# STorM32_NT_imu_module_v008-mpu6000.net
KiCad netlist of a schematic drawn in EAGLE
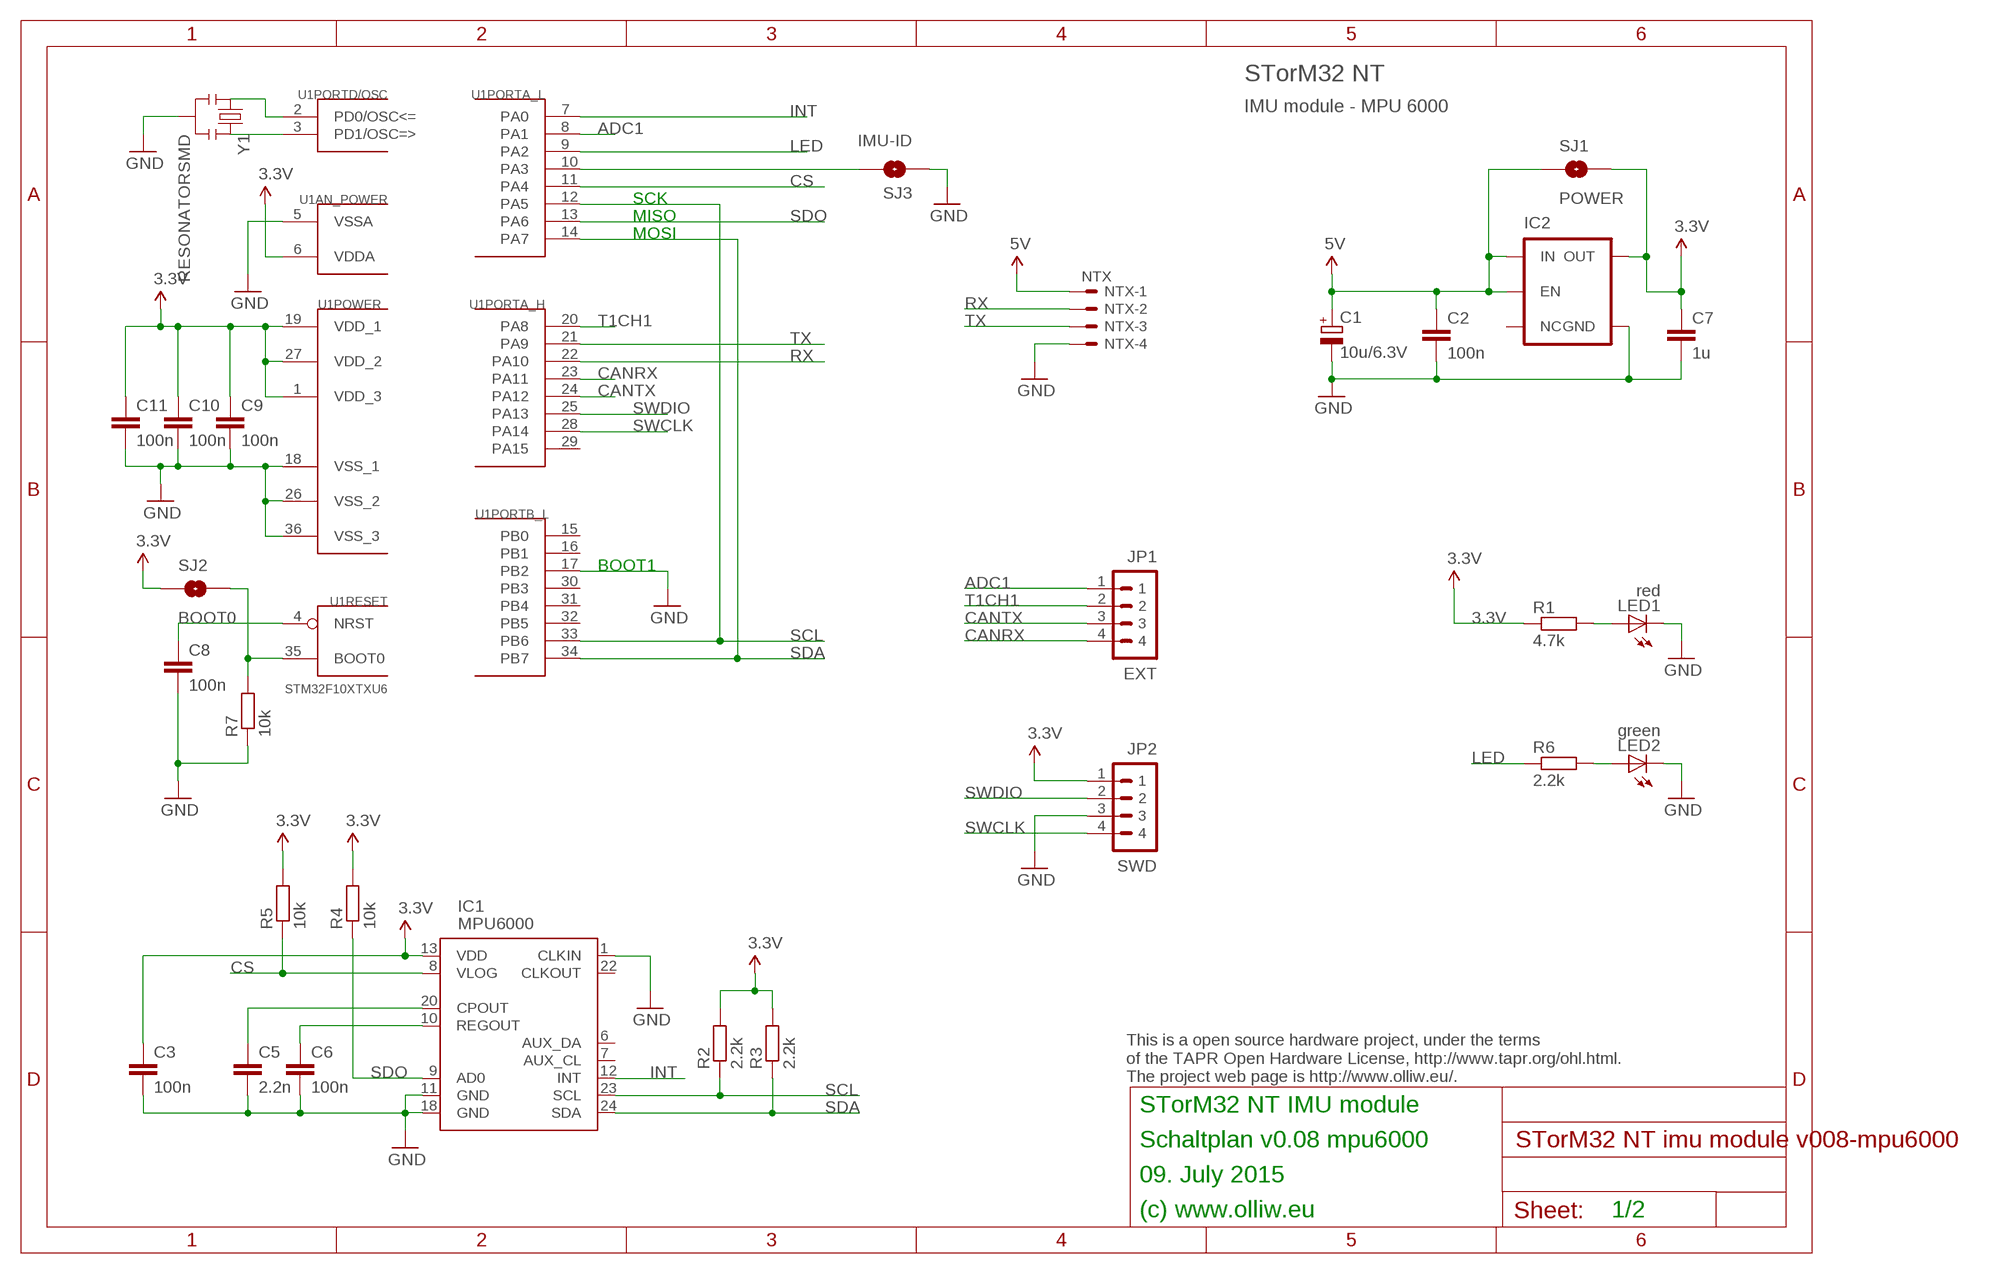
[diagram p0: schematic, sheet 1]

(export (version "E")
  (design (tool "Eeschema 10.0.6"))
  (components
    (comp (ref "C1")
      (value "10u/6.3V")
      (footprint "eagle-import:SMC_B")
      (libsource (lib "eagle-import") (part "CPOL-EUSMCB"))
    )
    (comp (ref "C2")
      (value "100n")
      (footprint "eagle-import:C0603")
      (libsource (lib "eagle-import") (part "C-EUC0603"))
    )
    (comp (ref "C3")
      (value "100n")
      (footprint "eagle-import:C0603")
      (libsource (lib "eagle-import") (part "C-EUC0603"))
    )
    (comp (ref "C5")
      (value "2.2n")
      (footprint "eagle-import:C0603")
      (libsource (lib "eagle-import") (part "C-EUC0603"))
    )
    (comp (ref "C6")
      (value "100n")
      (footprint "eagle-import:C0603")
      (libsource (lib "eagle-import") (part "C-EUC0603"))
    )
    (comp (ref "C7")
      (value "1u")
      (footprint "eagle-import:C0603")
      (libsource (lib "eagle-import") (part "C-EUC0603"))
    )
    (comp (ref "C8")
      (value "100n")
      (footprint "eagle-import:C0402")
      (libsource (lib "eagle-import") (part "C-EUC0402"))
    )
    (comp (ref "C9")
      (value "100n")
      (footprint "eagle-import:C0603")
      (libsource (lib "eagle-import") (part "C-EUC0603"))
    )
    (comp (ref "C10")
      (value "100n")
      (footprint "eagle-import:C0402")
      (libsource (lib "eagle-import") (part "C-EUC0402"))
    )
    (comp (ref "C11")
      (value "100n")
      (footprint "eagle-import:C0603")
      (libsource (lib "eagle-import") (part "C-EUC0603"))
    )
    (comp (ref "IC1")
      (value "MPU6000")
      (footprint "eagle-import:QFN-24")
      (libsource (lib "eagle-import") (part "IMU3000"))
    )
    (comp (ref "IC2")
      (value "V_REG_TPS76433SOT23-5")
      (footprint "eagle-import:SOT23-5")
      (libsource (lib "eagle-import") (part "V_REG_TPS76433SOT23-5"))
    )
    (comp (ref "JP1")
      (value "EXT")
      (footprint "eagle-import:4X1_1P27_OCT_BILEX")
      (libsource (lib "eagle-import") (part "P4X1_1P27-OCT_BILEX"))
    )
    (comp (ref "JP2")
      (value "SWD")
      (footprint "eagle-import:4X1_1P27_OCT_BILEX")
      (libsource (lib "eagle-import") (part "P4X1_1P27-OCT_BILEX"))
    )
    (comp (ref "LED1")
      (value "red")
      (footprint "eagle-import:CHIPLED_0603")
      (libsource (lib "eagle-import") (part "LEDCHIPLED_0603"))
    )
    (comp (ref "LED2")
      (value "green")
      (footprint "eagle-import:CHIPLED_0603")
      (libsource (lib "eagle-import") (part "LEDCHIPLED_0603"))
    )
    (comp (ref "NTX")
      (value "NTX")
      (footprint "eagle-import:SM04B-SRSS-TB")
      (libsource (lib "eagle-import") (part "?M04B-SRSS-TBS"))
    )
    (comp (ref "R1")
      (value "4.7k")
      (footprint "eagle-import:R0603")
      (libsource (lib "eagle-import") (part "R-EU_R0603"))
    )
    (comp (ref "R2")
      (value "2.2k")
      (footprint "eagle-import:R0603")
      (libsource (lib "eagle-import") (part "R-EU_R0603"))
    )
    (comp (ref "R3")
      (value "2.2k")
      (footprint "eagle-import:R0603")
      (libsource (lib "eagle-import") (part "R-EU_R0603"))
    )
    (comp (ref "R4")
      (value "10k")
      (footprint "eagle-import:R0603")
      (libsource (lib "eagle-import") (part "R-EU_R0603"))
    )
    (comp (ref "R5")
      (value "10k")
      (footprint "eagle-import:R0603")
      (libsource (lib "eagle-import") (part "R-EU_R0603"))
    )
    (comp (ref "R6")
      (value "2.2k")
      (footprint "eagle-import:R0603")
      (libsource (lib "eagle-import") (part "R-EU_R0603"))
    )
    (comp (ref "R7")
      (value "10k")
      (footprint "eagle-import:R0603")
      (libsource (lib "eagle-import") (part "R-EU_R0603"))
    )
    (comp (ref "SJ1")
      (value "POWER")
      (footprint "eagle-import:SJ_2S-NO")
      (libsource (lib "eagle-import") (part "SOLDERJUMPERNO"))
    )
    (comp (ref "SJ2")
      (value "BOOT0")
      (footprint "eagle-import:SJ_2S-NO")
      (libsource (lib "eagle-import") (part "SOLDERJUMPERNO"))
    )
    (comp (ref "SJ3")
      (value "IMU-ID")
      (footprint "eagle-import:SJ_2S-NO")
      (libsource (lib "eagle-import") (part "SOLDERJUMPERNO"))
    )
    (comp (ref "U1")
      (value "STM32F10XTXU6")
      (footprint "eagle-import:VFQFPN36")
      (libsource (lib "eagle-import") (part "STM32F10XTXU6"))
    )
    (comp (ref "Y1")
      (value "RESONATORSMD")
      (footprint "eagle-import:RESONATOR-SMD")
      (libsource (lib "eagle-import") (part "RESONATORSMD"))
    )
  )
  (nets
    (net (code "1") (name "/ADC1") (class "Default")
      (node (ref "JP1") (pin "1") (pinfunction "1_1") (pintype "passive"))
      (node (ref "U1") (pin "8") (pinfunction "PA1_8") (pintype "bidirectional"))
    )
    (net (code "2") (name "/CANRX") (class "Default")
      (node (ref "JP1") (pin "4") (pinfunction "4_4") (pintype "passive"))
      (node (ref "U1") (pin "23") (pinfunction "PA11_23") (pintype "bidirectional"))
    )
    (net (code "3") (name "/CANTX") (class "Default")
      (node (ref "JP1") (pin "3") (pinfunction "3_3") (pintype "passive"))
      (node (ref "U1") (pin "24") (pinfunction "PA12_24") (pintype "bidirectional"))
    )
    (net (code "4") (name "/CS") (class "Default")
      (node (ref "IC1") (pin "8") (pinfunction "VLOG_8") (pintype "bidirectional"))
      (node (ref "R5") (pin "1") (pinfunction "1_1") (pintype "passive"))
      (node (ref "U1") (pin "11") (pinfunction "PA4_11") (pintype "bidirectional"))
    )
    (net (code "5") (name "/INT") (class "Default")
      (node (ref "IC1") (pin "12") (pinfunction "INT_12") (pintype "bidirectional"))
      (node (ref "U1") (pin "7") (pinfunction "PA0_7") (pintype "bidirectional"))
    )
    (net (code "6") (name "/LED") (class "Default")
      (node (ref "R6") (pin "1") (pinfunction "1_1") (pintype "passive"))
      (node (ref "U1") (pin "9") (pinfunction "PA2_9") (pintype "bidirectional"))
    )
    (net (code "7") (name "/RX") (class "Default")
      (node (ref "NTX") (pin "2") (pinfunction "S_2") (pintype "passive"))
      (node (ref "U1") (pin "22") (pinfunction "PA10_22") (pintype "bidirectional"))
    )
    (net (code "8") (name "/SCL") (class "Default")
      (node (ref "IC1") (pin "23") (pinfunction "SCL_23") (pintype "bidirectional"))
      (node (ref "R2") (pin "1") (pinfunction "1_1") (pintype "passive"))
      (node (ref "U1") (pin "12") (pinfunction "PA5_12") (pintype "bidirectional"))
      (node (ref "U1") (pin "33") (pinfunction "PB6_33") (pintype "bidirectional"))
    )
    (net (code "9") (name "/SDA") (class "Default")
      (node (ref "IC1") (pin "24") (pinfunction "SDA_24") (pintype "bidirectional"))
      (node (ref "R3") (pin "1") (pinfunction "1_1") (pintype "passive"))
      (node (ref "U1") (pin "14") (pinfunction "PA7_14") (pintype "bidirectional"))
      (node (ref "U1") (pin "34") (pinfunction "PB7_34") (pintype "bidirectional"))
    )
    (net (code "10") (name "/SDO") (class "Default")
      (node (ref "IC1") (pin "9") (pinfunction "AD0_9") (pintype "bidirectional"))
      (node (ref "R4") (pin "1") (pinfunction "1_1") (pintype "passive"))
      (node (ref "U1") (pin "13") (pinfunction "PA6_13") (pintype "bidirectional"))
    )
    (net (code "11") (name "/SWCLK") (class "Default")
      (node (ref "JP2") (pin "4") (pinfunction "4_4") (pintype "passive"))
      (node (ref "U1") (pin "28") (pinfunction "PA14_28") (pintype "bidirectional"))
    )
    (net (code "12") (name "/SWDIO") (class "Default")
      (node (ref "JP2") (pin "2") (pinfunction "2_2") (pintype "passive"))
      (node (ref "U1") (pin "25") (pinfunction "PA13_25") (pintype "bidirectional"))
    )
    (net (code "13") (name "/T1CH1") (class "Default")
      (node (ref "JP1") (pin "2") (pinfunction "2_2") (pintype "passive"))
      (node (ref "U1") (pin "20") (pinfunction "PA8_20") (pintype "bidirectional"))
    )
    (net (code "14") (name "/TX") (class "Default")
      (node (ref "NTX") (pin "3") (pinfunction "S_3") (pintype "passive"))
      (node (ref "U1") (pin "21") (pinfunction "PA9_21") (pintype "bidirectional"))
    )
    (net (code "15") (name "3.3V") (class "Default")
      (node (ref "C10") (pin "1") (pinfunction "1_1") (pintype "passive"))
      (node (ref "C11") (pin "1") (pinfunction "1_1") (pintype "passive"))
      (node (ref "C3") (pin "1") (pinfunction "1_1") (pintype "passive"))
      (node (ref "C7") (pin "1") (pinfunction "1_1") (pintype "passive"))
      (node (ref "C9") (pin "1") (pinfunction "1_1") (pintype "passive"))
      (node (ref "IC1") (pin "13") (pinfunction "VDD_13") (pintype "bidirectional"))
      (node (ref "IC2") (pin "5") (pinfunction "OUT_5") (pintype "passive"))
      (node (ref "JP2") (pin "1") (pinfunction "1_1") (pintype "passive"))
      (node (ref "R1") (pin "1") (pinfunction "1_1") (pintype "passive"))
      (node (ref "R2") (pin "2") (pinfunction "2_2") (pintype "passive"))
      (node (ref "R3") (pin "2") (pinfunction "2_2") (pintype "passive"))
      (node (ref "R4") (pin "2") (pinfunction "2_2") (pintype "passive"))
      (node (ref "R5") (pin "2") (pinfunction "2_2") (pintype "passive"))
      (node (ref "SJ1") (pin "2") (pinfunction "2_2") (pintype "passive"))
      (node (ref "SJ2") (pin "1") (pinfunction "1_1") (pintype "passive"))
      (node (ref "U1") (pin "1") (pinfunction "VDD_3_1") (pintype "power_in"))
      (node (ref "U1") (pin "19") (pinfunction "VDD_1_19") (pintype "power_in"))
      (node (ref "U1") (pin "27") (pinfunction "VDD_2_27") (pintype "power_in"))
      (node (ref "U1") (pin "6") (pinfunction "VDDA_6") (pintype "power_in"))
    )
    (net (code "16") (name "5V") (class "Default")
      (node (ref "C1") (pin "+") (pinfunction "+_+") (pintype "passive"))
      (node (ref "C2") (pin "1") (pinfunction "1_1") (pintype "passive"))
      (node (ref "IC2") (pin "1") (pinfunction "IN_1") (pintype "input"))
      (node (ref "IC2") (pin "3") (pinfunction "EN_3") (pintype "input"))
      (node (ref "NTX") (pin "1") (pinfunction "S_1") (pintype "passive"))
      (node (ref "SJ1") (pin "1") (pinfunction "1_1") (pintype "passive"))
    )
    (net (code "17") (name "GND") (class "Default")
      (node (ref "C1") (pin "-") (pinfunction "-_-") (pintype "passive"))
      (node (ref "C10") (pin "2") (pinfunction "2_2") (pintype "passive"))
      (node (ref "C11") (pin "2") (pinfunction "2_2") (pintype "passive"))
      (node (ref "C2") (pin "2") (pinfunction "2_2") (pintype "passive"))
      (node (ref "C3") (pin "2") (pinfunction "2_2") (pintype "passive"))
      (node (ref "C5") (pin "2") (pinfunction "2_2") (pintype "passive"))
      (node (ref "C6") (pin "2") (pinfunction "2_2") (pintype "passive"))
      (node (ref "C7") (pin "2") (pinfunction "2_2") (pintype "passive"))
      (node (ref "C8") (pin "2") (pinfunction "2_2") (pintype "passive"))
      (node (ref "C9") (pin "2") (pinfunction "2_2") (pintype "passive"))
      (node (ref "IC1") (pin "1") (pinfunction "CLKIN_1") (pintype "bidirectional"))
      (node (ref "IC1") (pin "11") (pinfunction "GND_11") (pintype "bidirectional"))
      (node (ref "IC1") (pin "18") (pinfunction "GND_18") (pintype "bidirectional"))
      (node (ref "IC2") (pin "2") (pinfunction "GND_2") (pintype "input"))
      (node (ref "JP2") (pin "3") (pinfunction "3_3") (pintype "passive"))
      (node (ref "LED1") (pin "C") (pinfunction "C_C") (pintype "passive"))
      (node (ref "LED2") (pin "C") (pinfunction "C_C") (pintype "passive"))
      (node (ref "NTX") (pin "4") (pinfunction "S_4") (pintype "passive"))
      (node (ref "R7") (pin "1") (pinfunction "1_1") (pintype "passive"))
      (node (ref "SJ3") (pin "1") (pinfunction "1_1") (pintype "passive"))
      (node (ref "U1") (pin "17") (pinfunction "PB2_17") (pintype "bidirectional"))
      (node (ref "U1") (pin "18") (pinfunction "VSS_1_18") (pintype "power_in"))
      (node (ref "U1") (pin "26") (pinfunction "VSS_2_26") (pintype "power_in"))
      (node (ref "U1") (pin "36") (pinfunction "VSS_3_36") (pintype "power_in"))
      (node (ref "U1") (pin "5") (pinfunction "VSSA_5") (pintype "power_in"))
      (node (ref "Y1") (pin "2") (pinfunction "2_2") (pintype "passive"))
    )
    (net (code "18") (name "Net-(IC1-CPOUT)") (class "Default")
      (node (ref "C5") (pin "1") (pinfunction "1_1") (pintype "passive"))
      (node (ref "IC1") (pin "20") (pinfunction "CPOUT_20") (pintype "bidirectional"))
    )
    (net (code "19") (name "Net-(IC1-REGOUT)") (class "Default")
      (node (ref "C6") (pin "1") (pinfunction "1_1") (pintype "passive"))
      (node (ref "IC1") (pin "10") (pinfunction "REGOUT_10") (pintype "bidirectional"))
    )
    (net (code "20") (name "Net-(LED1-PadA)") (class "Default")
      (node (ref "LED1") (pin "A") (pinfunction "A_A") (pintype "passive"))
      (node (ref "R1") (pin "2") (pinfunction "2_2") (pintype "passive"))
    )
    (net (code "21") (name "Net-(LED2-PadA)") (class "Default")
      (node (ref "LED2") (pin "A") (pinfunction "A_A") (pintype "passive"))
      (node (ref "R6") (pin "2") (pinfunction "2_2") (pintype "passive"))
    )
    (net (code "22") (name "Net-(U1C-PA3)") (class "Default")
      (node (ref "SJ3") (pin "2") (pinfunction "2_2") (pintype "passive"))
      (node (ref "U1") (pin "10") (pinfunction "PA3_10") (pintype "bidirectional"))
    )
    (net (code "23") (name "Net-(U1E-PD0{slash}OSC<=)") (class "Default")
      (node (ref "U1") (pin "2") (pinfunction "PD0/OSC<=_2") (pintype "bidirectional"))
      (node (ref "Y1") (pin "1") (pinfunction "1_1") (pintype "passive"))
    )
    (net (code "24") (name "Net-(U1E-PD1{slash}OSC=>)") (class "Default")
      (node (ref "U1") (pin "3") (pinfunction "PD1/OSC=>_3") (pintype "bidirectional"))
      (node (ref "Y1") (pin "3") (pinfunction "3_3") (pintype "passive"))
    )
    (net (code "25") (name "Net-(U1G-BOOT0)") (class "Default")
      (node (ref "R7") (pin "2") (pinfunction "2_2") (pintype "passive"))
      (node (ref "SJ2") (pin "2") (pinfunction "2_2") (pintype "passive"))
      (node (ref "U1") (pin "35") (pinfunction "BOOT0_35") (pintype "input"))
    )
    (net (code "26") (name "Net-(U1G-NRST)") (class "Default")
      (node (ref "C8") (pin "1") (pinfunction "1_1") (pintype "passive"))
      (node (ref "U1") (pin "4") (pinfunction "NRST_4") (pintype "input"))
    )
    (net (code "27") (name "unconnected-(IC1-AUX_CL-Pad7)") (class "Default")
      (node (ref "IC1") (pin "7") (pinfunction "AUX_CL_7") (pintype "bidirectional"))
    )
    (net (code "28") (name "unconnected-(IC1-AUX_DA-Pad6)") (class "Default")
      (node (ref "IC1") (pin "6") (pinfunction "AUX_DA_6") (pintype "bidirectional"))
    )
    (net (code "29") (name "unconnected-(IC1-CLKOUT-Pad22)") (class "Default")
      (node (ref "IC1") (pin "22") (pinfunction "CLKOUT_22") (pintype "bidirectional"))
    )
    (net (code "30") (name "unconnected-(IC2-NC-Pad4)") (class "Default")
      (node (ref "IC2") (pin "4") (pinfunction "NC_4") (pintype "input"))
    )
    (net (code "31") (name "unconnected-(U1B-PA15-Pad29)") (class "Default")
      (node (ref "U1") (pin "29") (pinfunction "PA15_29") (pintype "bidirectional"))
    )
    (net (code "32") (name "unconnected-(U1D-PB0-Pad15)") (class "Default")
      (node (ref "U1") (pin "15") (pinfunction "PB0_15") (pintype "bidirectional"))
    )
    (net (code "33") (name "unconnected-(U1D-PB1-Pad16)") (class "Default")
      (node (ref "U1") (pin "16") (pinfunction "PB1_16") (pintype "bidirectional"))
    )
    (net (code "34") (name "unconnected-(U1D-PB3-Pad30)") (class "Default")
      (node (ref "U1") (pin "30") (pinfunction "PB3_30") (pintype "bidirectional"))
    )
    (net (code "35") (name "unconnected-(U1D-PB4-Pad31)") (class "Default")
      (node (ref "U1") (pin "31") (pinfunction "PB4_31") (pintype "bidirectional"))
    )
    (net (code "36") (name "unconnected-(U1D-PB5-Pad32)") (class "Default")
      (node (ref "U1") (pin "32") (pinfunction "PB5_32") (pintype "bidirectional"))
    )
  )
)
